# LC-meter.net
KiCad netlist of a schematic drawn in EAGLE
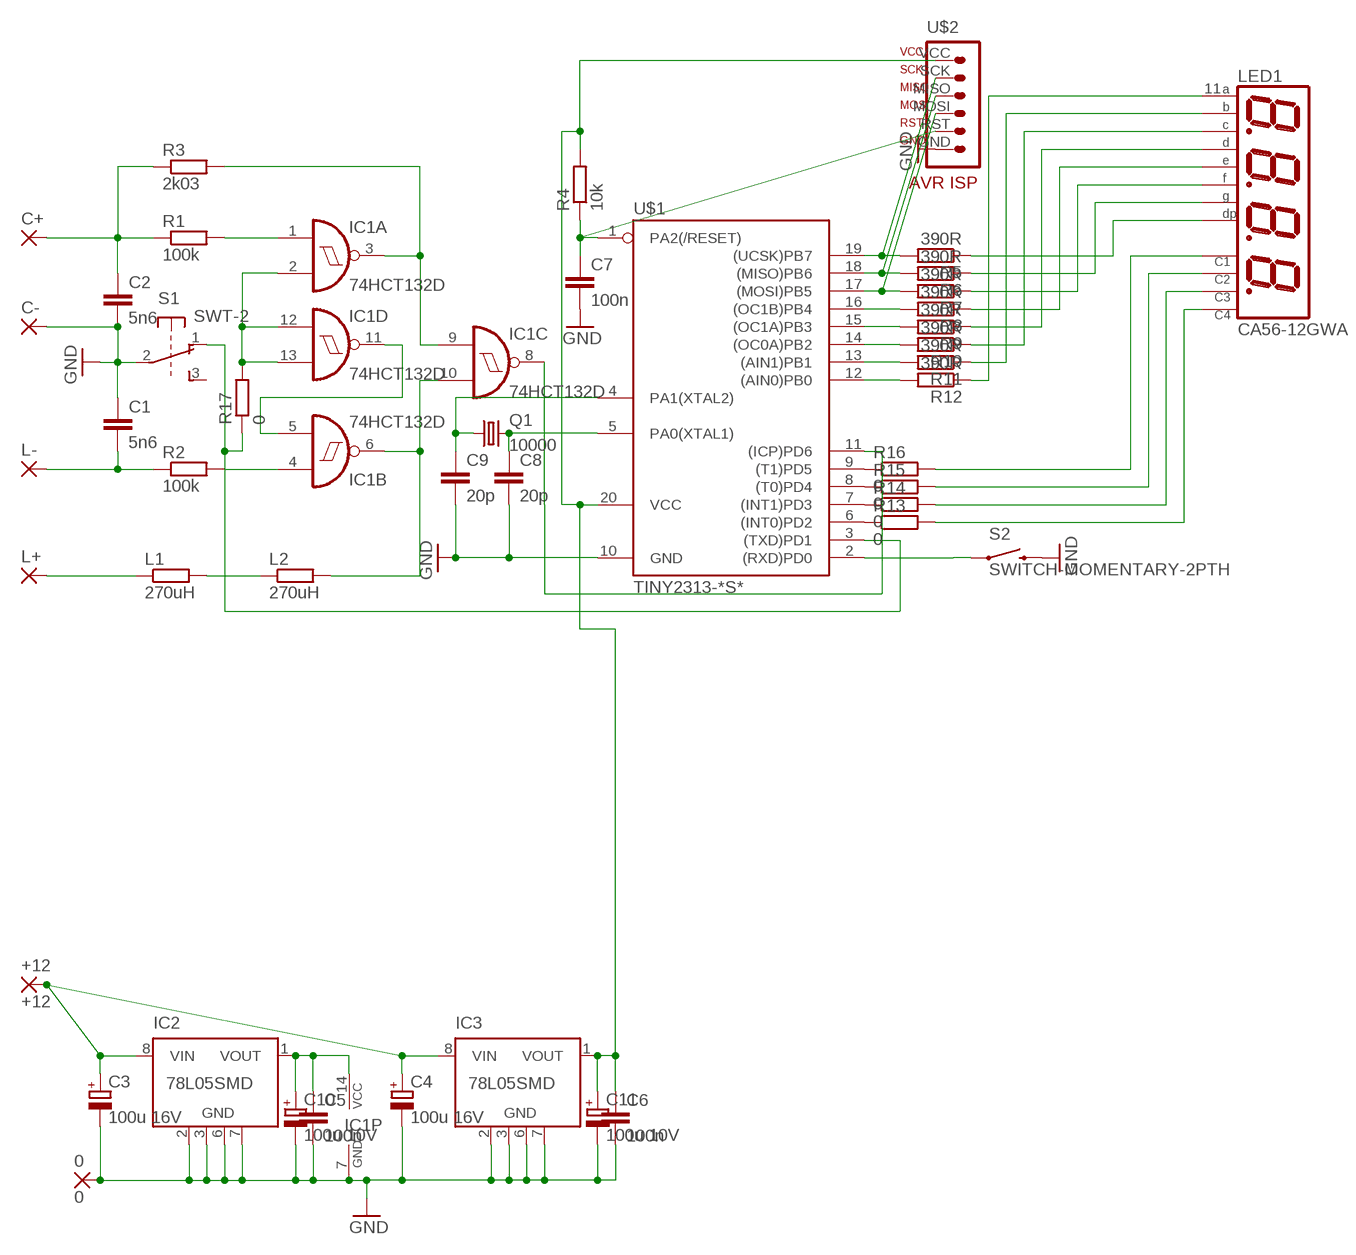
[diagram p0: schematic, sheet 1]

(export (version "E")
  (design (tool "Eeschema 10.0.6"))
  (components
    (comp (ref "+12")
      (value "+12")
      (footprint "eagle-import:3,17_1,1")
      (libsource (lib "eagle-import") (part "3,17/1,1"))
    )
    (comp (ref "0")
      (value "0")
      (footprint "eagle-import:3,17_1,1")
      (libsource (lib "eagle-import") (part "3,17/1,1"))
    )
    (comp (ref "C+")
      (value "3,17/1,1")
      (footprint "eagle-import:3,17_1,1")
      (libsource (lib "eagle-import") (part "3,17/1,1"))
    )
    (comp (ref "C-")
      (value "3,17/1,1")
      (footprint "eagle-import:3,17_1,1")
      (libsource (lib "eagle-import") (part "3,17/1,1"))
    )
    (comp (ref "C1")
      (value "5n6")
      (footprint "eagle-import:C0805")
      (libsource (lib "eagle-import") (part "C-EUC0805"))
    )
    (comp (ref "C2")
      (value "5n6")
      (footprint "eagle-import:C0805")
      (libsource (lib "eagle-import") (part "C-EUC0805"))
    )
    (comp (ref "C3")
      (value "100u 16V")
      (footprint "eagle-import:E2,5-7")
      (libsource (lib "eagle-import") (part "CPOL-EUE2.5-7"))
    )
    (comp (ref "C4")
      (value "100u 16V")
      (footprint "eagle-import:E2,5-7")
      (libsource (lib "eagle-import") (part "CPOL-EUE2.5-7"))
    )
    (comp (ref "C5")
      (value "100n")
      (footprint "eagle-import:C0805")
      (libsource (lib "eagle-import") (part "C-EUC0805"))
    )
    (comp (ref "C6")
      (value "100n")
      (footprint "eagle-import:C0805")
      (libsource (lib "eagle-import") (part "C-EUC0805"))
    )
    (comp (ref "C7")
      (value "100n")
      (footprint "eagle-import:C0805")
      (libsource (lib "eagle-import") (part "C-EUC0805"))
    )
    (comp (ref "C8")
      (value "20p")
      (footprint "eagle-import:C1206")
      (libsource (lib "eagle-import") (part "C-EUC1206"))
    )
    (comp (ref "C9")
      (value "20p")
      (footprint "eagle-import:C1206")
      (libsource (lib "eagle-import") (part "C-EUC1206"))
    )
    (comp (ref "C10")
      (value "100u 10V")
      (footprint "eagle-import:E2,5-7")
      (libsource (lib "eagle-import") (part "CPOL-EUE2.5-7"))
    )
    (comp (ref "C11")
      (value "100u 10V")
      (footprint "eagle-import:E2,5-7")
      (libsource (lib "eagle-import") (part "CPOL-EUE2.5-7"))
    )
    (comp (ref "IC1")
      (value "74HCT132D")
      (footprint "eagle-import:SO14")
      (libsource (lib "eagle-import") (part "74132DHCT"))
    )
    (comp (ref "IC2")
      (value "78L05SMD")
      (footprint "eagle-import:SO08")
      (libsource (lib "eagle-import") (part "78LSMD05"))
    )
    (comp (ref "IC3")
      (value "78L05SMD")
      (footprint "eagle-import:SO08")
      (libsource (lib "eagle-import") (part "78LSMD05"))
    )
    (comp (ref "L+")
      (value "3,17/1,1")
      (footprint "eagle-import:3,17_1,1")
      (libsource (lib "eagle-import") (part "3,17/1,1"))
    )
    (comp (ref "L-")
      (value "3,17/1,1")
      (footprint "eagle-import:3,17_1,1")
      (libsource (lib "eagle-import") (part "3,17/1,1"))
    )
    (comp (ref "L1")
      (value "270uH")
      (footprint "eagle-import:R1210")
      (libsource (lib "eagle-import") (part "R-EU_R1210"))
    )
    (comp (ref "L2")
      (value "270uH")
      (footprint "eagle-import:R1210")
      (libsource (lib "eagle-import") (part "R-EU_R1210"))
    )
    (comp (ref "LED1")
      (value "CA56-12GWA")
      (footprint "eagle-import:0,56_4X7SEG_LED")
      (libsource (lib "eagle-import") (part "CA56-12GWA"))
    )
    (comp (ref "Q1")
      (value "10000")
      (footprint "eagle-import:HC49_S")
      (libsource (lib "eagle-import") (part "CRYSTALHC49S"))
    )
    (comp (ref "R1")
      (value "100k")
      (footprint "eagle-import:R1206")
      (libsource (lib "eagle-import") (part "R-EU_R1206"))
    )
    (comp (ref "R2")
      (value "100k")
      (footprint "eagle-import:R1206")
      (libsource (lib "eagle-import") (part "R-EU_R1206"))
    )
    (comp (ref "R3")
      (value "2k03")
      (footprint "eagle-import:R1206")
      (libsource (lib "eagle-import") (part "R-EU_R1206"))
    )
    (comp (ref "R4")
      (value "10k")
      (footprint "eagle-import:R1206")
      (libsource (lib "eagle-import") (part "R-EU_R1206"))
    )
    (comp (ref "R5")
      (value "390R")
      (footprint "eagle-import:R1206")
      (libsource (lib "eagle-import") (part "R-EU_R1206"))
    )
    (comp (ref "R6")
      (value "390R")
      (footprint "eagle-import:R1206")
      (libsource (lib "eagle-import") (part "R-EU_R1206"))
    )
    (comp (ref "R7")
      (value "390R")
      (footprint "eagle-import:R1206")
      (libsource (lib "eagle-import") (part "R-EU_R1206"))
    )
    (comp (ref "R8")
      (value "390R")
      (footprint "eagle-import:R1206")
      (libsource (lib "eagle-import") (part "R-EU_R1206"))
    )
    (comp (ref "R9")
      (value "390R")
      (footprint "eagle-import:R1206")
      (libsource (lib "eagle-import") (part "R-EU_R1206"))
    )
    (comp (ref "R10")
      (value "390R")
      (footprint "eagle-import:R1206")
      (libsource (lib "eagle-import") (part "R-EU_R1206"))
    )
    (comp (ref "R11")
      (value "390R")
      (footprint "eagle-import:R1206")
      (libsource (lib "eagle-import") (part "R-EU_R1206"))
    )
    (comp (ref "R12")
      (value "390R")
      (footprint "eagle-import:R1206")
      (libsource (lib "eagle-import") (part "R-EU_R1206"))
    )
    (comp (ref "R13")
      (value "0")
      (footprint "eagle-import:R1206")
      (libsource (lib "eagle-import") (part "R-EU_R1206"))
    )
    (comp (ref "R14")
      (value "0")
      (footprint "eagle-import:R1206")
      (libsource (lib "eagle-import") (part "R-EU_R1206"))
    )
    (comp (ref "R15")
      (value "0")
      (footprint "eagle-import:R1206")
      (libsource (lib "eagle-import") (part "R-EU_R1206"))
    )
    (comp (ref "R16")
      (value "0")
      (footprint "eagle-import:R1206")
      (libsource (lib "eagle-import") (part "R-EU_R1206"))
    )
    (comp (ref "R17")
      (value "0")
      (footprint "eagle-import:R1206")
      (libsource (lib "eagle-import") (part "R-EU_R1206"))
    )
    (comp (ref "S1")
      (value "SWT-2")
      (footprint "eagle-import:SWT-2")
      (libsource (lib "eagle-import") (part "SWT-2"))
    )
    (comp (ref "S2")
      (value "SWITCH-MOMENTARY-2PTH")
      (footprint "eagle-import:TACTILE-PTH")
      (libsource (lib "eagle-import") (part "SWITCH-MOMENTARY-2PTH"))
    )
    (comp (ref "U$1")
      (value "TINY2313-*S*")
      (footprint "eagle-import:SO20L$")
      (libsource (lib "eagle-import") (part "TINY2313-S"))
    )
    (comp (ref "U$2")
      (value "AVR-ISP-6-ROW")
      (footprint "eagle-import:AVR-ISP-6-ROW")
      (libsource (lib "eagle-import") (part "AVR-ISP-6-ROW"))
    )
  )
  (nets
    (net (code "1") (name "GND") (class "Default")
      (node (ref "0") (pin "1") (pinfunction "P_1") (pintype "passive"))
      (node (ref "C-") (pin "1") (pinfunction "P_1") (pintype "passive"))
      (node (ref "C1") (pin "1") (pinfunction "1_1") (pintype "passive"))
      (node (ref "C10") (pin "-") (pinfunction "-_-") (pintype "passive"))
      (node (ref "C11") (pin "-") (pinfunction "-_-") (pintype "passive"))
      (node (ref "C2") (pin "2") (pinfunction "2_2") (pintype "passive"))
      (node (ref "C3") (pin "-") (pinfunction "-_-") (pintype "passive"))
      (node (ref "C4") (pin "-") (pinfunction "-_-") (pintype "passive"))
      (node (ref "C5") (pin "2") (pinfunction "2_2") (pintype "passive"))
      (node (ref "C6") (pin "2") (pinfunction "2_2") (pintype "passive"))
      (node (ref "C7") (pin "2") (pinfunction "2_2") (pintype "passive"))
      (node (ref "C8") (pin "2") (pinfunction "2_2") (pintype "passive"))
      (node (ref "C9") (pin "2") (pinfunction "2_2") (pintype "passive"))
      (node (ref "IC1") (pin "7") (pinfunction "GND_7") (pintype "power_in"))
      (node (ref "IC2") (pin "2") (pinfunction "GND_2") (pintype "power_in"))
      (node (ref "IC2") (pin "3") (pinfunction "GND_3") (pintype "power_in"))
      (node (ref "IC2") (pin "6") (pinfunction "GND_6") (pintype "power_in"))
      (node (ref "IC2") (pin "7") (pinfunction "GND_7") (pintype "power_in"))
      (node (ref "IC3") (pin "2") (pinfunction "GND_2") (pintype "power_in"))
      (node (ref "IC3") (pin "3") (pinfunction "GND_3") (pintype "power_in"))
      (node (ref "IC3") (pin "6") (pinfunction "GND_6") (pintype "power_in"))
      (node (ref "IC3") (pin "7") (pinfunction "GND_7") (pintype "power_in"))
      (node (ref "S1") (pin "2") (pinfunction "2_2") (pintype "passive"))
      (node (ref "S2") (pin "3") (pinfunction "2_3") (pintype "passive"))
      (node (ref "U$1") (pin "10") (pinfunction "GND_10") (pintype "power_in"))
      (node (ref "U$2") (pin "GND") (pinfunction "GND_GND") (pintype "passive"))
    )
    (net (code "2") (name "Net-(+12-P)") (class "Default")
      (node (ref "+12") (pin "1") (pinfunction "P_1") (pintype "passive"))
      (node (ref "C3") (pin "+") (pinfunction "+_+") (pintype "passive"))
      (node (ref "C4") (pin "+") (pinfunction "+_+") (pintype "passive"))
      (node (ref "IC2") (pin "8") (pinfunction "VIN_8") (pintype "passive"))
      (node (ref "IC3") (pin "8") (pinfunction "VIN_8") (pintype "passive"))
    )
    (net (code "3") (name "Net-(C+-P)") (class "Default")
      (node (ref "C+") (pin "1") (pinfunction "P_1") (pintype "passive"))
      (node (ref "C2") (pin "1") (pinfunction "1_1") (pintype "passive"))
      (node (ref "R1") (pin "1") (pinfunction "1_1") (pintype "passive"))
      (node (ref "R3") (pin "1") (pinfunction "1_1") (pintype "passive"))
    )
    (net (code "4") (name "Net-(IC1A-I0)") (class "Default")
      (node (ref "IC1") (pin "1") (pinfunction "I0_1") (pintype "input"))
      (node (ref "R1") (pin "2") (pinfunction "2_2") (pintype "passive"))
    )
    (net (code "5") (name "Net-(IC1A-I1)") (class "Default")
      (node (ref "IC1") (pin "12") (pinfunction "I0_12") (pintype "input"))
      (node (ref "IC1") (pin "13") (pinfunction "I1_13") (pintype "input"))
      (node (ref "IC1") (pin "2") (pinfunction "I1_2") (pintype "input"))
      (node (ref "R17") (pin "2") (pinfunction "2_2") (pintype "passive"))
    )
    (net (code "6") (name "Net-(IC1A-O)") (class "Default")
      (node (ref "IC1") (pin "3") (pinfunction "O_3") (pintype "output"))
      (node (ref "IC1") (pin "9") (pinfunction "I0_9") (pintype "input"))
      (node (ref "R3") (pin "2") (pinfunction "2_2") (pintype "passive"))
    )
    (net (code "7") (name "Net-(IC1B-I0)") (class "Default")
      (node (ref "IC1") (pin "4") (pinfunction "I0_4") (pintype "input"))
      (node (ref "R2") (pin "2") (pinfunction "2_2") (pintype "passive"))
    )
    (net (code "8") (name "Net-(IC1B-I1)") (class "Default")
      (node (ref "IC1") (pin "11") (pinfunction "O_11") (pintype "output"))
      (node (ref "IC1") (pin "5") (pinfunction "I1_5") (pintype "input"))
    )
    (net (code "9") (name "Net-(IC1B-O)") (class "Default")
      (node (ref "IC1") (pin "10") (pinfunction "I1_10") (pintype "input"))
      (node (ref "IC1") (pin "6") (pinfunction "O_6") (pintype "output"))
      (node (ref "L2") (pin "2") (pinfunction "2_2") (pintype "passive"))
    )
    (net (code "10") (name "Net-(IC1C-O)") (class "Default")
      (node (ref "IC1") (pin "8") (pinfunction "O_8") (pintype "output"))
      (node (ref "U$1") (pin "11") (pinfunction "(ICP)PD6_11") (pintype "bidirectional"))
    )
    (net (code "11") (name "Net-(IC1E-VCC)") (class "Default")
      (node (ref "C10") (pin "+") (pinfunction "+_+") (pintype "passive"))
      (node (ref "C5") (pin "1") (pinfunction "1_1") (pintype "passive"))
      (node (ref "IC1") (pin "14") (pinfunction "VCC_14") (pintype "power_in"))
      (node (ref "IC2") (pin "1") (pinfunction "VOUT_1") (pintype "output"))
    )
    (net (code "12") (name "Net-(IC3A-VOUT)") (class "Default")
      (node (ref "C11") (pin "+") (pinfunction "+_+") (pintype "passive"))
      (node (ref "C6") (pin "1") (pinfunction "1_1") (pintype "passive"))
      (node (ref "IC3") (pin "1") (pinfunction "VOUT_1") (pintype "output"))
      (node (ref "R4") (pin "2") (pinfunction "2_2") (pintype "passive"))
      (node (ref "U$1") (pin "20") (pinfunction "VCC_20") (pintype "power_in"))
      (node (ref "U$2") (pin "VCC") (pinfunction "VCC_VCC") (pintype "passive"))
    )
    (net (code "13") (name "Net-(L+-P)") (class "Default")
      (node (ref "L+") (pin "1") (pinfunction "P_1") (pintype "passive"))
      (node (ref "L1") (pin "1") (pinfunction "1_1") (pintype "passive"))
    )
    (net (code "14") (name "Net-(L--P)") (class "Default")
      (node (ref "C1") (pin "2") (pinfunction "2_2") (pintype "passive"))
      (node (ref "L-") (pin "1") (pinfunction "P_1") (pintype "passive"))
      (node (ref "R2") (pin "1") (pinfunction "1_1") (pintype "passive"))
    )
    (net (code "15") (name "Net-(L1-Pad2)") (class "Default")
      (node (ref "L1") (pin "2") (pinfunction "2_2") (pintype "passive"))
      (node (ref "L2") (pin "1") (pinfunction "1_1") (pintype "passive"))
    )
    (net (code "16") (name "Net-(LED1-A)") (class "Default")
      (node (ref "LED1") (pin "11") (pinfunction "A_11") (pintype "passive"))
      (node (ref "R12") (pin "1") (pinfunction "1_1") (pintype "passive"))
    )
    (net (code "17") (name "Net-(LED1-A1)") (class "Default")
      (node (ref "LED1") (pin "12") (pinfunction "A1_12") (pintype "bidirectional"))
      (node (ref "R16") (pin "2") (pinfunction "2_2") (pintype "passive"))
    )
    (net (code "18") (name "Net-(LED1-A2)") (class "Default")
      (node (ref "LED1") (pin "9") (pinfunction "A2_9") (pintype "bidirectional"))
      (node (ref "R15") (pin "2") (pinfunction "2_2") (pintype "passive"))
    )
    (net (code "19") (name "Net-(LED1-A3)") (class "Default")
      (node (ref "LED1") (pin "8") (pinfunction "A3_8") (pintype "bidirectional"))
      (node (ref "R14") (pin "2") (pinfunction "2_2") (pintype "passive"))
    )
    (net (code "20") (name "Net-(LED1-A4)") (class "Default")
      (node (ref "LED1") (pin "6") (pinfunction "A4_6") (pintype "bidirectional"))
      (node (ref "R13") (pin "2") (pinfunction "2_2") (pintype "passive"))
    )
    (net (code "21") (name "Net-(LED1-B)") (class "Default")
      (node (ref "LED1") (pin "7") (pinfunction "B_7") (pintype "passive"))
      (node (ref "R11") (pin "1") (pinfunction "1_1") (pintype "passive"))
    )
    (net (code "22") (name "Net-(LED1-C)") (class "Default")
      (node (ref "LED1") (pin "4") (pinfunction "C_4") (pintype "passive"))
      (node (ref "R10") (pin "1") (pinfunction "1_1") (pintype "passive"))
    )
    (net (code "23") (name "Net-(LED1-D)") (class "Default")
      (node (ref "LED1") (pin "2") (pinfunction "D_2") (pintype "passive"))
      (node (ref "R9") (pin "1") (pinfunction "1_1") (pintype "passive"))
    )
    (net (code "24") (name "Net-(LED1-DP)") (class "Default")
      (node (ref "LED1") (pin "3") (pinfunction "DP_3") (pintype "passive"))
      (node (ref "R5") (pin "1") (pinfunction "1_1") (pintype "passive"))
    )
    (net (code "25") (name "Net-(LED1-E)") (class "Default")
      (node (ref "LED1") (pin "1") (pinfunction "E_1") (pintype "passive"))
      (node (ref "R8") (pin "1") (pinfunction "1_1") (pintype "passive"))
    )
    (net (code "26") (name "Net-(LED1-F)") (class "Default")
      (node (ref "LED1") (pin "10") (pinfunction "F_10") (pintype "passive"))
      (node (ref "R7") (pin "1") (pinfunction "1_1") (pintype "passive"))
    )
    (net (code "27") (name "Net-(LED1-G)") (class "Default")
      (node (ref "LED1") (pin "5") (pinfunction "G_5") (pintype "passive"))
      (node (ref "R6") (pin "1") (pinfunction "1_1") (pintype "passive"))
    )
    (net (code "28") (name "Net-(U$1-(AIN0)PB0)") (class "Default")
      (node (ref "R12") (pin "2") (pinfunction "2_2") (pintype "passive"))
      (node (ref "U$1") (pin "12") (pinfunction "(AIN0)PB0_12") (pintype "bidirectional"))
    )
    (net (code "29") (name "Net-(U$1-(AIN1)PB1)") (class "Default")
      (node (ref "R11") (pin "2") (pinfunction "2_2") (pintype "passive"))
      (node (ref "U$1") (pin "13") (pinfunction "(AIN1)PB1_13") (pintype "bidirectional"))
    )
    (net (code "30") (name "Net-(U$1-(INT0)PD2)") (class "Default")
      (node (ref "R13") (pin "1") (pinfunction "1_1") (pintype "passive"))
      (node (ref "U$1") (pin "6") (pinfunction "(INT0)PD2_6") (pintype "bidirectional"))
    )
    (net (code "31") (name "Net-(U$1-(INT1)PD3)") (class "Default")
      (node (ref "R14") (pin "1") (pinfunction "1_1") (pintype "passive"))
      (node (ref "U$1") (pin "7") (pinfunction "(INT1)PD3_7") (pintype "bidirectional"))
    )
    (net (code "32") (name "Net-(U$1-(MISO)PB6)") (class "Default")
      (node (ref "R6") (pin "2") (pinfunction "2_2") (pintype "passive"))
      (node (ref "U$1") (pin "18") (pinfunction "(MISO)PB6_18") (pintype "bidirectional"))
      (node (ref "U$2") (pin "MISO") (pinfunction "MISO_MISO") (pintype "passive"))
    )
    (net (code "33") (name "Net-(U$1-(MOSI)PB5)") (class "Default")
      (node (ref "R7") (pin "2") (pinfunction "2_2") (pintype "passive"))
      (node (ref "U$1") (pin "17") (pinfunction "(MOSI)PB5_17") (pintype "bidirectional"))
      (node (ref "U$2") (pin "MOSI") (pinfunction "MOSI_MOSI") (pintype "passive"))
    )
    (net (code "34") (name "Net-(U$1-(OC0A)PB2)") (class "Default")
      (node (ref "R10") (pin "2") (pinfunction "2_2") (pintype "passive"))
      (node (ref "U$1") (pin "14") (pinfunction "(OC0A)PB2_14") (pintype "bidirectional"))
    )
    (net (code "35") (name "Net-(U$1-(OC1A)PB3)") (class "Default")
      (node (ref "R9") (pin "2") (pinfunction "2_2") (pintype "passive"))
      (node (ref "U$1") (pin "15") (pinfunction "(OC1A)PB3_15") (pintype "bidirectional"))
    )
    (net (code "36") (name "Net-(U$1-(OC1B)PB4)") (class "Default")
      (node (ref "R8") (pin "2") (pinfunction "2_2") (pintype "passive"))
      (node (ref "U$1") (pin "16") (pinfunction "(OC1B)PB4_16") (pintype "bidirectional"))
    )
    (net (code "37") (name "Net-(U$1-(RXD)PD0)") (class "Default")
      (node (ref "S2") (pin "1") (pinfunction "1_1") (pintype "passive"))
      (node (ref "U$1") (pin "2") (pinfunction "(RXD)PD0_2") (pintype "bidirectional"))
    )
    (net (code "38") (name "Net-(U$1-(T0)PD4)") (class "Default")
      (node (ref "R15") (pin "1") (pinfunction "1_1") (pintype "passive"))
      (node (ref "U$1") (pin "8") (pinfunction "(T0)PD4_8") (pintype "bidirectional"))
    )
    (net (code "39") (name "Net-(U$1-(T1)PD5)") (class "Default")
      (node (ref "R16") (pin "1") (pinfunction "1_1") (pintype "passive"))
      (node (ref "U$1") (pin "9") (pinfunction "(T1)PD5_9") (pintype "bidirectional"))
    )
    (net (code "40") (name "Net-(U$1-(TXD)PD1)") (class "Default")
      (node (ref "R17") (pin "1") (pinfunction "1_1") (pintype "passive"))
      (node (ref "S1") (pin "1") (pinfunction "1_1") (pintype "passive"))
      (node (ref "U$1") (pin "3") (pinfunction "(TXD)PD1_3") (pintype "bidirectional"))
    )
    (net (code "41") (name "Net-(U$1-(UCSK)PB7)") (class "Default")
      (node (ref "R5") (pin "2") (pinfunction "2_2") (pintype "passive"))
      (node (ref "U$1") (pin "19") (pinfunction "(UCSK)PB7_19") (pintype "bidirectional"))
      (node (ref "U$2") (pin "SCK") (pinfunction "SCK_SCK") (pintype "passive"))
    )
    (net (code "42") (name "Net-(U$1-PA0(XTAL1))") (class "Default")
      (node (ref "C8") (pin "1") (pinfunction "1_1") (pintype "passive"))
      (node (ref "Q1") (pin "2") (pinfunction "2_2") (pintype "passive"))
      (node (ref "U$1") (pin "5") (pinfunction "PA0(XTAL1)_5") (pintype "bidirectional"))
    )
    (net (code "43") (name "Net-(U$1-PA1(XTAL2))") (class "Default")
      (node (ref "C9") (pin "1") (pinfunction "1_1") (pintype "passive"))
      (node (ref "Q1") (pin "1") (pinfunction "1_1") (pintype "passive"))
      (node (ref "U$1") (pin "4") (pinfunction "PA1(XTAL2)_4") (pintype "bidirectional"))
    )
    (net (code "44") (name "Net-(U$1-PA2({slash}RESET))") (class "Default")
      (node (ref "C7") (pin "1") (pinfunction "1_1") (pintype "passive"))
      (node (ref "R4") (pin "1") (pinfunction "1_1") (pintype "passive"))
      (node (ref "U$1") (pin "1") (pinfunction "PA2(/RESET)_1") (pintype "input"))
      (node (ref "U$2") (pin "RST") (pinfunction "RST_RST") (pintype "passive"))
    )
    (net (code "45") (name "unconnected-(S1-Pad3)") (class "Default")
      (node (ref "S1") (pin "3") (pinfunction "3_3") (pintype "passive"))
    )
  )
)
